# untitled.net
KiCad netlist of a schematic drawn in EAGLE
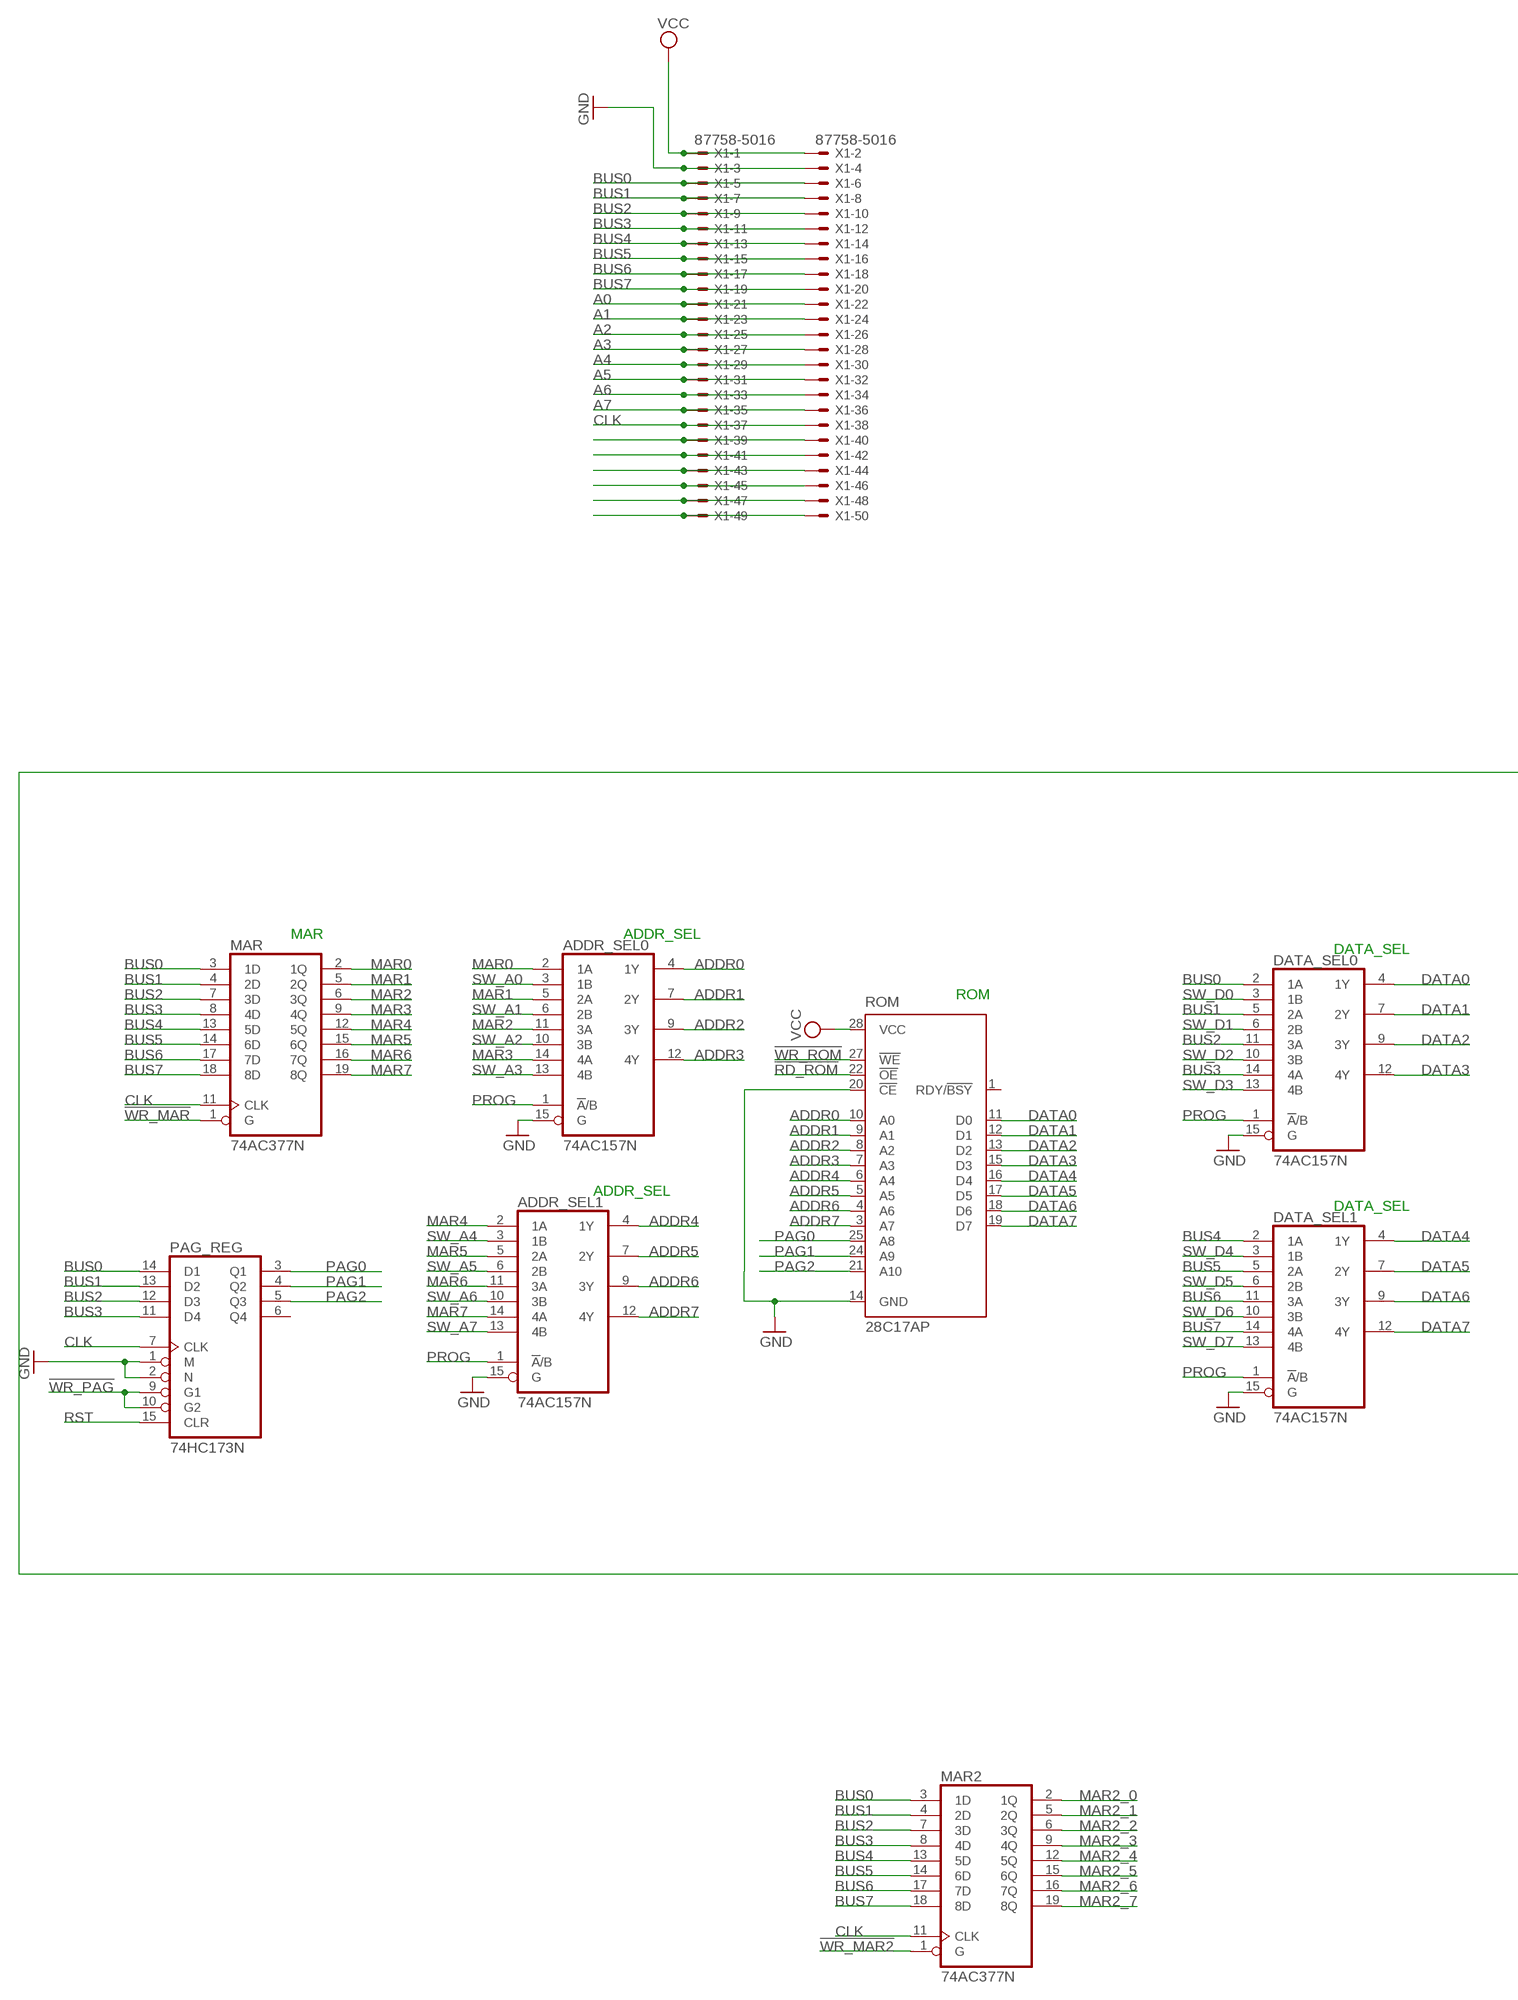
[diagram p0: schematic, sheet 1, part 1 of 2]
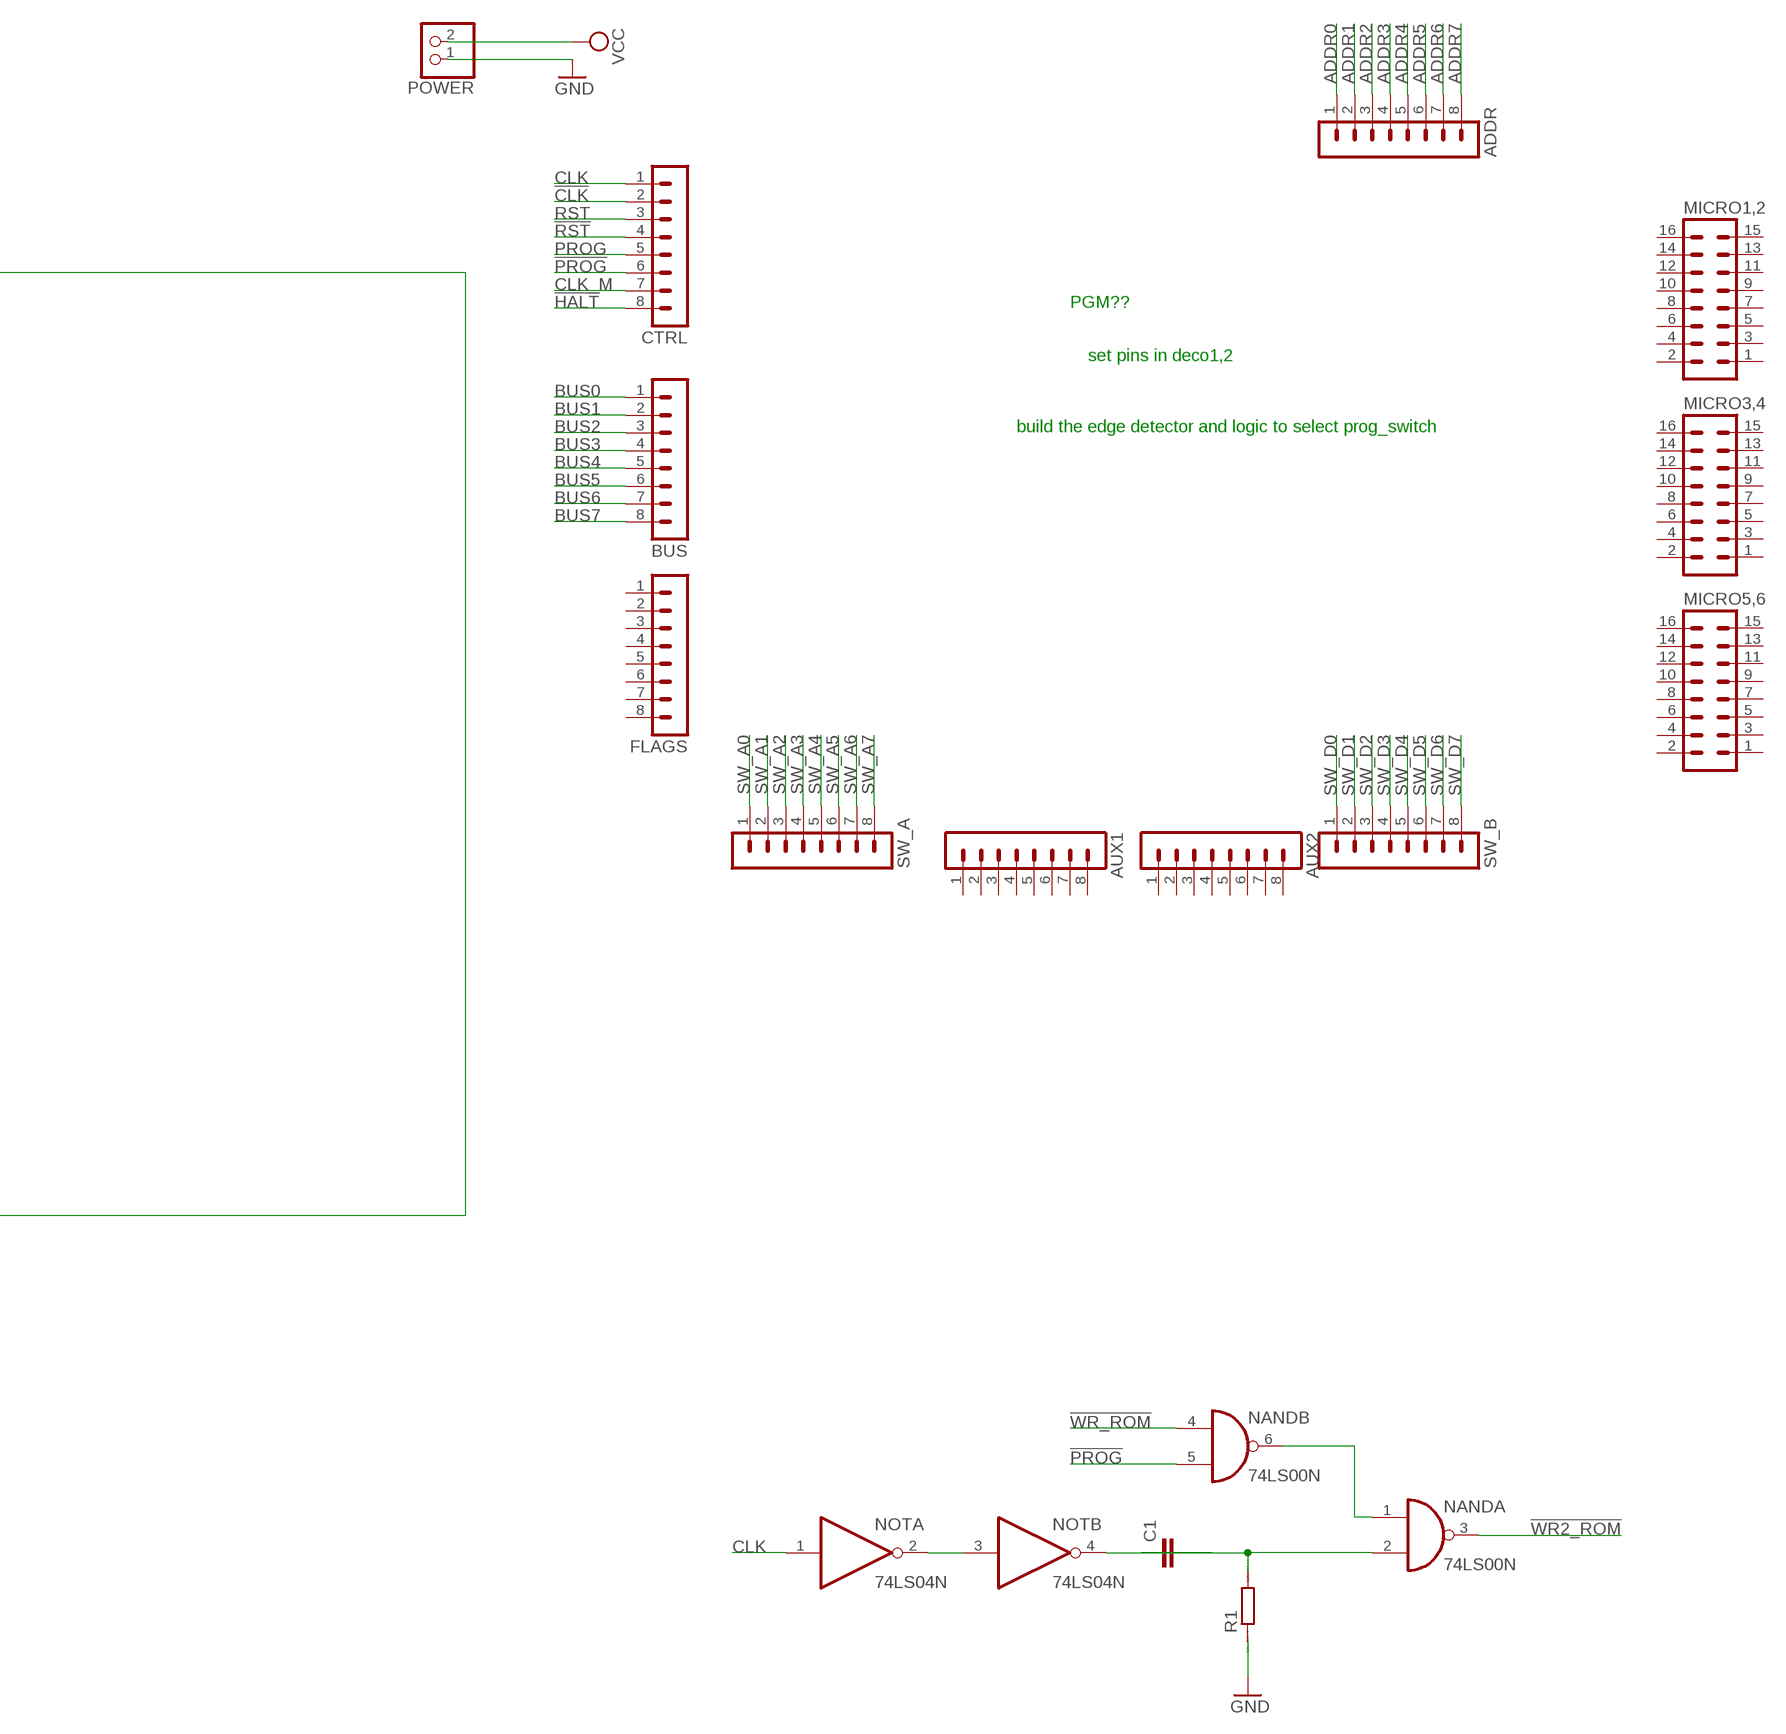
[diagram p1: schematic, sheet 1, part 2 of 2]

(export (version "E")
  (design (tool "Eeschema 10.0.6"))
  (components
    (comp (ref "ADDR")
      (value "MA08-1")
      (footprint "eagle-import:MA08-1")
      (libsource (lib "eagle-import") (part "MA08-1"))
    )
    (comp (ref "ADDR_SEL0")
      (value "74AC157N")
      (footprint "eagle-import:DIL16")
      (libsource (lib "eagle-import") (part "74157NAC"))
    )
    (comp (ref "ADDR_SEL1")
      (value "74AC157N")
      (footprint "eagle-import:DIL16")
      (libsource (lib "eagle-import") (part "74157NAC"))
    )
    (comp (ref "AUX1")
      (value "MA08-1")
      (footprint "eagle-import:MA08-1")
      (libsource (lib "eagle-import") (part "MA08-1"))
    )
    (comp (ref "AUX2")
      (value "MA08-1")
      (footprint "eagle-import:MA08-1")
      (libsource (lib "eagle-import") (part "MA08-1"))
    )
    (comp (ref "BUS")
      (value "MA08-1")
      (footprint "eagle-import:MA08-1")
      (libsource (lib "eagle-import") (part "MA08-1"))
    )
    (comp (ref "C1")
      (value "C2.5/4")
      (footprint "eagle-import:C2.5-4")
      (libsource (lib "eagle-import") (part "C2.5/4"))
    )
    (comp (ref "CTRL")
      (value "MA08-1")
      (footprint "eagle-import:MA08-1")
      (libsource (lib "eagle-import") (part "MA08-1"))
    )
    (comp (ref "DATA_SEL0")
      (value "74AC157N")
      (footprint "eagle-import:DIL16")
      (libsource (lib "eagle-import") (part "74157NAC"))
    )
    (comp (ref "DATA_SEL1")
      (value "74AC157N")
      (footprint "eagle-import:DIL16")
      (libsource (lib "eagle-import") (part "74157NAC"))
    )
    (comp (ref "FLAGS")
      (value "MA08-1")
      (footprint "eagle-import:MA08-1")
      (libsource (lib "eagle-import") (part "MA08-1"))
    )
    (comp (ref "MAR")
      (value "74AC377N")
      (footprint "eagle-import:DIL20")
      (libsource (lib "eagle-import") (part "74377NAC"))
    )
    (comp (ref "MAR2")
      (value "74AC377N")
      (footprint "eagle-import:DIL20")
      (libsource (lib "eagle-import") (part "74377NAC"))
    )
    (comp (ref "MICRO1,2")
      (value "MA08-2")
      (footprint "eagle-import:MA08-2")
      (libsource (lib "eagle-import") (part "MA08-2"))
    )
    (comp (ref "MICRO3,4")
      (value "MA08-2")
      (footprint "eagle-import:MA08-2")
      (libsource (lib "eagle-import") (part "MA08-2"))
    )
    (comp (ref "MICRO5,6")
      (value "MA08-2")
      (footprint "eagle-import:MA08-2")
      (libsource (lib "eagle-import") (part "MA08-2"))
    )
    (comp (ref "NAND")
      (value "74LS00N")
      (footprint "eagle-import:DIL14")
      (libsource (lib "eagle-import") (part "7400NLS"))
    )
    (comp (ref "NOT")
      (value "74LS04N")
      (footprint "eagle-import:DIL14")
      (libsource (lib "eagle-import") (part "7404NLS"))
    )
    (comp (ref "PAG_REG")
      (value "74HC173N")
      (footprint "eagle-import:DIL16")
      (libsource (lib "eagle-import") (part "74173NHC"))
    )
    (comp (ref "POWER")
      (value "PINHD-1X2")
      (footprint "eagle-import:1X02")
      (libsource (lib "eagle-import") (part "PINHD-1X2"))
    )
    (comp (ref "R1")
      (value "R0207/10")
      (footprint "eagle-import:0207_10")
      (libsource (lib "eagle-import") (part "R0207/10"))
    )
    (comp (ref "ROM")
      (value "28C17AP")
      (footprint "eagle-import:DIL28-6")
      (fields (field (name "MPN") "CAT28C17ALI20"))
      (libsource (lib "eagle-import") (part "2817APC"))
    )
    (comp (ref "SW_A")
      (value "MA08-1")
      (footprint "eagle-import:MA08-1")
      (libsource (lib "eagle-import") (part "MA08-1"))
    )
    (comp (ref "SW_B")
      (value "MA08-1")
      (footprint "eagle-import:MA08-1")
      (libsource (lib "eagle-import") (part "MA08-1"))
    )
    (comp (ref "X1")
      (value "87758-5016")
      (footprint "eagle-import:87758-5016")
      (fields (field (name "MF") "MOLEX"))
      (libsource (lib "eagle-import") (part "87758-5016"))
    )
  )
  (nets
    (net (code "1") (name "A0") (class "Default")
      (node (ref "X1") (pin "21") (pinfunction "S_21") (pintype "passive"))
      (node (ref "X1") (pin "22") (pinfunction "S_22") (pintype "passive"))
    )
    (net (code "2") (name "A1") (class "Default")
      (node (ref "X1") (pin "23") (pinfunction "S_23") (pintype "passive"))
      (node (ref "X1") (pin "24") (pinfunction "S_24") (pintype "passive"))
    )
    (net (code "3") (name "A2") (class "Default")
      (node (ref "X1") (pin "25") (pinfunction "S_25") (pintype "passive"))
      (node (ref "X1") (pin "26") (pinfunction "S_26") (pintype "passive"))
    )
    (net (code "4") (name "A3") (class "Default")
      (node (ref "X1") (pin "27") (pinfunction "S_27") (pintype "passive"))
      (node (ref "X1") (pin "28") (pinfunction "S_28") (pintype "passive"))
    )
    (net (code "5") (name "A4") (class "Default")
      (node (ref "X1") (pin "29") (pinfunction "S_29") (pintype "passive"))
      (node (ref "X1") (pin "30") (pinfunction "S_30") (pintype "passive"))
    )
    (net (code "6") (name "A5") (class "Default")
      (node (ref "X1") (pin "31") (pinfunction "S_31") (pintype "passive"))
      (node (ref "X1") (pin "32") (pinfunction "S_32") (pintype "passive"))
    )
    (net (code "7") (name "A6") (class "Default")
      (node (ref "X1") (pin "33") (pinfunction "S_33") (pintype "passive"))
      (node (ref "X1") (pin "34") (pinfunction "S_34") (pintype "passive"))
    )
    (net (code "8") (name "A7") (class "Default")
      (node (ref "X1") (pin "35") (pinfunction "S_35") (pintype "passive"))
      (node (ref "X1") (pin "36") (pinfunction "S_36") (pintype "passive"))
    )
    (net (code "9") (name "ADDR0") (class "Default")
      (node (ref "ADDR") (pin "1") (pinfunction "1_1") (pintype "passive"))
      (node (ref "ADDR_SEL0") (pin "4") (pinfunction "1Y_4") (pintype "output"))
      (node (ref "ROM") (pin "10") (pinfunction "A0_10") (pintype "input"))
    )
    (net (code "10") (name "ADDR1") (class "Default")
      (node (ref "ADDR") (pin "2") (pinfunction "2_2") (pintype "passive"))
      (node (ref "ADDR_SEL0") (pin "7") (pinfunction "2Y_7") (pintype "output"))
      (node (ref "ROM") (pin "9") (pinfunction "A1_9") (pintype "input"))
    )
    (net (code "11") (name "ADDR2") (class "Default")
      (node (ref "ADDR") (pin "3") (pinfunction "3_3") (pintype "passive"))
      (node (ref "ADDR_SEL0") (pin "9") (pinfunction "3Y_9") (pintype "output"))
      (node (ref "ROM") (pin "8") (pinfunction "A2_8") (pintype "input"))
    )
    (net (code "12") (name "ADDR3") (class "Default")
      (node (ref "ADDR") (pin "4") (pinfunction "4_4") (pintype "passive"))
      (node (ref "ADDR_SEL0") (pin "12") (pinfunction "4Y_12") (pintype "output"))
      (node (ref "ROM") (pin "7") (pinfunction "A3_7") (pintype "input"))
    )
    (net (code "13") (name "ADDR4") (class "Default")
      (node (ref "ADDR") (pin "5") (pinfunction "5_5") (pintype "passive"))
      (node (ref "ADDR_SEL1") (pin "4") (pinfunction "1Y_4") (pintype "output"))
      (node (ref "ROM") (pin "6") (pinfunction "A4_6") (pintype "input"))
    )
    (net (code "14") (name "ADDR5") (class "Default")
      (node (ref "ADDR") (pin "6") (pinfunction "6_6") (pintype "passive"))
      (node (ref "ADDR_SEL1") (pin "7") (pinfunction "2Y_7") (pintype "output"))
      (node (ref "ROM") (pin "5") (pinfunction "A5_5") (pintype "input"))
    )
    (net (code "15") (name "ADDR6") (class "Default")
      (node (ref "ADDR") (pin "7") (pinfunction "7_7") (pintype "passive"))
      (node (ref "ADDR_SEL1") (pin "9") (pinfunction "3Y_9") (pintype "output"))
      (node (ref "ROM") (pin "4") (pinfunction "A6_4") (pintype "input"))
    )
    (net (code "16") (name "ADDR7") (class "Default")
      (node (ref "ADDR") (pin "8") (pinfunction "8_8") (pintype "passive"))
      (node (ref "ADDR_SEL1") (pin "12") (pinfunction "4Y_12") (pintype "output"))
      (node (ref "ROM") (pin "3") (pinfunction "A7_3") (pintype "input"))
    )
    (net (code "17") (name "BUS0") (class "Default")
      (node (ref "BUS") (pin "1") (pinfunction "1_1") (pintype "passive"))
      (node (ref "DATA_SEL0") (pin "2") (pinfunction "1A_2") (pintype "input"))
      (node (ref "MAR") (pin "3") (pinfunction "1D_3") (pintype "input"))
      (node (ref "MAR2") (pin "3") (pinfunction "1D_3") (pintype "input"))
      (node (ref "PAG_REG") (pin "14") (pinfunction "D1_14") (pintype "input"))
      (node (ref "X1") (pin "5") (pinfunction "S_5") (pintype "passive"))
      (node (ref "X1") (pin "6") (pinfunction "S_6") (pintype "passive"))
    )
    (net (code "18") (name "BUS1") (class "Default")
      (node (ref "BUS") (pin "2") (pinfunction "2_2") (pintype "passive"))
      (node (ref "DATA_SEL0") (pin "5") (pinfunction "2A_5") (pintype "input"))
      (node (ref "MAR") (pin "4") (pinfunction "2D_4") (pintype "input"))
      (node (ref "MAR2") (pin "4") (pinfunction "2D_4") (pintype "input"))
      (node (ref "PAG_REG") (pin "13") (pinfunction "D2_13") (pintype "input"))
      (node (ref "X1") (pin "7") (pinfunction "S_7") (pintype "passive"))
      (node (ref "X1") (pin "8") (pinfunction "S_8") (pintype "passive"))
    )
    (net (code "19") (name "BUS2") (class "Default")
      (node (ref "BUS") (pin "3") (pinfunction "3_3") (pintype "passive"))
      (node (ref "DATA_SEL0") (pin "11") (pinfunction "3A_11") (pintype "input"))
      (node (ref "MAR") (pin "7") (pinfunction "3D_7") (pintype "input"))
      (node (ref "MAR2") (pin "7") (pinfunction "3D_7") (pintype "input"))
      (node (ref "PAG_REG") (pin "12") (pinfunction "D3_12") (pintype "input"))
      (node (ref "X1") (pin "10") (pinfunction "S_10") (pintype "passive"))
      (node (ref "X1") (pin "9") (pinfunction "S_9") (pintype "passive"))
    )
    (net (code "20") (name "BUS3") (class "Default")
      (node (ref "BUS") (pin "4") (pinfunction "4_4") (pintype "passive"))
      (node (ref "DATA_SEL0") (pin "14") (pinfunction "4A_14") (pintype "input"))
      (node (ref "MAR") (pin "8") (pinfunction "4D_8") (pintype "input"))
      (node (ref "MAR2") (pin "8") (pinfunction "4D_8") (pintype "input"))
      (node (ref "PAG_REG") (pin "11") (pinfunction "D4_11") (pintype "input"))
      (node (ref "X1") (pin "11") (pinfunction "S_11") (pintype "passive"))
      (node (ref "X1") (pin "12") (pinfunction "S_12") (pintype "passive"))
    )
    (net (code "21") (name "BUS4") (class "Default")
      (node (ref "BUS") (pin "5") (pinfunction "5_5") (pintype "passive"))
      (node (ref "DATA_SEL1") (pin "2") (pinfunction "1A_2") (pintype "input"))
      (node (ref "MAR") (pin "13") (pinfunction "5D_13") (pintype "input"))
      (node (ref "MAR2") (pin "13") (pinfunction "5D_13") (pintype "input"))
      (node (ref "X1") (pin "13") (pinfunction "S_13") (pintype "passive"))
      (node (ref "X1") (pin "14") (pinfunction "S_14") (pintype "passive"))
    )
    (net (code "22") (name "BUS5") (class "Default")
      (node (ref "BUS") (pin "6") (pinfunction "6_6") (pintype "passive"))
      (node (ref "DATA_SEL1") (pin "5") (pinfunction "2A_5") (pintype "input"))
      (node (ref "MAR") (pin "14") (pinfunction "6D_14") (pintype "input"))
      (node (ref "MAR2") (pin "14") (pinfunction "6D_14") (pintype "input"))
      (node (ref "X1") (pin "15") (pinfunction "S_15") (pintype "passive"))
      (node (ref "X1") (pin "16") (pinfunction "S_16") (pintype "passive"))
    )
    (net (code "23") (name "BUS6") (class "Default")
      (node (ref "BUS") (pin "7") (pinfunction "7_7") (pintype "passive"))
      (node (ref "DATA_SEL1") (pin "11") (pinfunction "3A_11") (pintype "input"))
      (node (ref "MAR") (pin "17") (pinfunction "7D_17") (pintype "input"))
      (node (ref "MAR2") (pin "17") (pinfunction "7D_17") (pintype "input"))
      (node (ref "X1") (pin "17") (pinfunction "S_17") (pintype "passive"))
      (node (ref "X1") (pin "18") (pinfunction "S_18") (pintype "passive"))
    )
    (net (code "24") (name "BUS7") (class "Default")
      (node (ref "BUS") (pin "8") (pinfunction "8_8") (pintype "passive"))
      (node (ref "DATA_SEL1") (pin "14") (pinfunction "4A_14") (pintype "input"))
      (node (ref "MAR") (pin "18") (pinfunction "8D_18") (pintype "input"))
      (node (ref "MAR2") (pin "18") (pinfunction "8D_18") (pintype "input"))
      (node (ref "X1") (pin "19") (pinfunction "S_19") (pintype "passive"))
      (node (ref "X1") (pin "20") (pinfunction "S_20") (pintype "passive"))
    )
    (net (code "25") (name "CLK") (class "Default")
      (node (ref "CTRL") (pin "1") (pinfunction "1_1") (pintype "passive"))
      (node (ref "MAR") (pin "11") (pinfunction "CLK_11") (pintype "input"))
      (node (ref "MAR2") (pin "11") (pinfunction "CLK_11") (pintype "input"))
      (node (ref "NOT") (pin "1") (pinfunction "I_1") (pintype "input"))
      (node (ref "PAG_REG") (pin "7") (pinfunction "CLK_7") (pintype "input"))
      (node (ref "X1") (pin "37") (pinfunction "S_37") (pintype "passive"))
      (node (ref "X1") (pin "38") (pinfunction "S_38") (pintype "passive"))
    )
    (net (code "26") (name "CLK_M") (class "Default")
      (node (ref "CTRL") (pin "7") (pinfunction "7_7") (pintype "passive"))
    )
    (net (code "27") (name "DATA0") (class "Default")
      (node (ref "DATA_SEL0") (pin "4") (pinfunction "1Y_4") (pintype "output"))
      (node (ref "ROM") (pin "11") (pinfunction "D0_11") (pintype "tri_state"))
    )
    (net (code "28") (name "DATA1") (class "Default")
      (node (ref "DATA_SEL0") (pin "7") (pinfunction "2Y_7") (pintype "output"))
      (node (ref "ROM") (pin "12") (pinfunction "D1_12") (pintype "tri_state"))
    )
    (net (code "29") (name "DATA2") (class "Default")
      (node (ref "DATA_SEL0") (pin "9") (pinfunction "3Y_9") (pintype "output"))
      (node (ref "ROM") (pin "13") (pinfunction "D2_13") (pintype "tri_state"))
    )
    (net (code "30") (name "DATA3") (class "Default")
      (node (ref "DATA_SEL0") (pin "12") (pinfunction "4Y_12") (pintype "output"))
      (node (ref "ROM") (pin "15") (pinfunction "D3_15") (pintype "tri_state"))
    )
    (net (code "31") (name "DATA4") (class "Default")
      (node (ref "DATA_SEL1") (pin "4") (pinfunction "1Y_4") (pintype "output"))
      (node (ref "ROM") (pin "16") (pinfunction "D4_16") (pintype "tri_state"))
    )
    (net (code "32") (name "DATA5") (class "Default")
      (node (ref "DATA_SEL1") (pin "7") (pinfunction "2Y_7") (pintype "output"))
      (node (ref "ROM") (pin "17") (pinfunction "D5_17") (pintype "tri_state"))
    )
    (net (code "33") (name "DATA6") (class "Default")
      (node (ref "DATA_SEL1") (pin "9") (pinfunction "3Y_9") (pintype "output"))
      (node (ref "ROM") (pin "18") (pinfunction "D6_18") (pintype "tri_state"))
    )
    (net (code "34") (name "DATA7") (class "Default")
      (node (ref "DATA_SEL1") (pin "12") (pinfunction "4Y_12") (pintype "output"))
      (node (ref "ROM") (pin "19") (pinfunction "D7_19") (pintype "tri_state"))
    )
    (net (code "35") (name "GND") (class "Default")
      (node (ref "ADDR_SEL0") (pin "15") (pinfunction "G_15") (pintype "input"))
      (node (ref "ADDR_SEL1") (pin "15") (pinfunction "G_15") (pintype "input"))
      (node (ref "DATA_SEL0") (pin "15") (pinfunction "G_15") (pintype "input"))
      (node (ref "DATA_SEL1") (pin "15") (pinfunction "G_15") (pintype "input"))
      (node (ref "PAG_REG") (pin "1") (pinfunction "M_1") (pintype "input"))
      (node (ref "PAG_REG") (pin "2") (pinfunction "N_2") (pintype "input"))
      (node (ref "POWER") (pin "1") (pinfunction "1_1") (pintype "passive"))
      (node (ref "R1") (pin "1") (pinfunction "1_1") (pintype "passive"))
      (node (ref "ROM") (pin "14") (pinfunction "GND_14") (pintype "power_in"))
      (node (ref "ROM") (pin "20") (pinfunction "~{CE}_20") (pintype "input"))
      (node (ref "X1") (pin "3") (pinfunction "S_3") (pintype "passive"))
      (node (ref "X1") (pin "4") (pinfunction "S_4") (pintype "passive"))
    )
    (net (code "36") (name "MAR0") (class "Default")
      (node (ref "ADDR_SEL0") (pin "2") (pinfunction "1A_2") (pintype "input"))
      (node (ref "MAR") (pin "2") (pinfunction "1Q_2") (pintype "output"))
    )
    (net (code "37") (name "MAR1") (class "Default")
      (node (ref "ADDR_SEL0") (pin "5") (pinfunction "2A_5") (pintype "input"))
      (node (ref "MAR") (pin "5") (pinfunction "2Q_5") (pintype "output"))
    )
    (net (code "38") (name "MAR2") (class "Default")
      (node (ref "ADDR_SEL0") (pin "11") (pinfunction "3A_11") (pintype "input"))
      (node (ref "MAR") (pin "6") (pinfunction "3Q_6") (pintype "output"))
    )
    (net (code "39") (name "MAR2_0") (class "Default")
      (node (ref "MAR2") (pin "2") (pinfunction "1Q_2") (pintype "output"))
    )
    (net (code "40") (name "MAR2_1") (class "Default")
      (node (ref "MAR2") (pin "5") (pinfunction "2Q_5") (pintype "output"))
    )
    (net (code "41") (name "MAR2_2") (class "Default")
      (node (ref "MAR2") (pin "6") (pinfunction "3Q_6") (pintype "output"))
    )
    (net (code "42") (name "MAR2_3") (class "Default")
      (node (ref "MAR2") (pin "9") (pinfunction "4Q_9") (pintype "output"))
    )
    (net (code "43") (name "MAR2_4") (class "Default")
      (node (ref "MAR2") (pin "12") (pinfunction "5Q_12") (pintype "output"))
    )
    (net (code "44") (name "MAR2_5") (class "Default")
      (node (ref "MAR2") (pin "15") (pinfunction "6Q_15") (pintype "output"))
    )
    (net (code "45") (name "MAR2_6") (class "Default")
      (node (ref "MAR2") (pin "16") (pinfunction "7Q_16") (pintype "output"))
    )
    (net (code "46") (name "MAR2_7") (class "Default")
      (node (ref "MAR2") (pin "19") (pinfunction "8Q_19") (pintype "output"))
    )
    (net (code "47") (name "MAR3") (class "Default")
      (node (ref "ADDR_SEL0") (pin "14") (pinfunction "4A_14") (pintype "input"))
      (node (ref "MAR") (pin "9") (pinfunction "4Q_9") (pintype "output"))
    )
    (net (code "48") (name "MAR4") (class "Default")
      (node (ref "ADDR_SEL1") (pin "2") (pinfunction "1A_2") (pintype "input"))
      (node (ref "MAR") (pin "12") (pinfunction "5Q_12") (pintype "output"))
    )
    (net (code "49") (name "MAR5") (class "Default")
      (node (ref "ADDR_SEL1") (pin "5") (pinfunction "2A_5") (pintype "input"))
      (node (ref "MAR") (pin "15") (pinfunction "6Q_15") (pintype "output"))
    )
    (net (code "50") (name "MAR6") (class "Default")
      (node (ref "ADDR_SEL1") (pin "11") (pinfunction "3A_11") (pintype "input"))
      (node (ref "MAR") (pin "16") (pinfunction "7Q_16") (pintype "output"))
    )
    (net (code "51") (name "MAR7") (class "Default")
      (node (ref "ADDR_SEL1") (pin "14") (pinfunction "4A_14") (pintype "input"))
      (node (ref "MAR") (pin "19") (pinfunction "8Q_19") (pintype "output"))
    )
    (net (code "52") (name "Net-(NANDA-I0)") (class "Default")
      (node (ref "NAND") (pin "1") (pinfunction "I0_1") (pintype "input"))
      (node (ref "NAND") (pin "6") (pinfunction "O_6") (pintype "output"))
    )
    (net (code "53") (name "Net-(NANDA-I1)") (class "Default")
      (node (ref "C1") (pin "2") (pinfunction "2_2") (pintype "passive"))
      (node (ref "NAND") (pin "2") (pinfunction "I1_2") (pintype "input"))
      (node (ref "R1") (pin "2") (pinfunction "2_2") (pintype "passive"))
    )
    (net (code "54") (name "Net-(NOTA-O)") (class "Default")
      (node (ref "NOT") (pin "2") (pinfunction "O_2") (pintype "output"))
      (node (ref "NOT") (pin "3") (pinfunction "I_3") (pintype "input"))
    )
    (net (code "55") (name "Net-(NOTB-O)") (class "Default")
      (node (ref "C1") (pin "1") (pinfunction "1_1") (pintype "passive"))
      (node (ref "NOT") (pin "4") (pinfunction "O_4") (pintype "output"))
    )
    (net (code "56") (name "Net-(X1AG-S)") (class "Default")
      (node (ref "X1") (pin "39") (pinfunction "S_39") (pintype "passive"))
      (node (ref "X1") (pin "40") (pinfunction "S_40") (pintype "passive"))
    )
    (net (code "57") (name "Net-(X1AJ-S)") (class "Default")
      (node (ref "X1") (pin "41") (pinfunction "S_41") (pintype "passive"))
      (node (ref "X1") (pin "42") (pinfunction "S_42") (pintype "passive"))
    )
    (net (code "58") (name "Net-(X1AL-S)") (class "Default")
      (node (ref "X1") (pin "43") (pinfunction "S_43") (pintype "passive"))
      (node (ref "X1") (pin "44") (pinfunction "S_44") (pintype "passive"))
    )
    (net (code "59") (name "Net-(X1AN-S)") (class "Default")
      (node (ref "X1") (pin "45") (pinfunction "S_45") (pintype "passive"))
      (node (ref "X1") (pin "46") (pinfunction "S_46") (pintype "passive"))
    )
    (net (code "60") (name "Net-(X1AP-S)") (class "Default")
      (node (ref "X1") (pin "47") (pinfunction "S_47") (pintype "passive"))
      (node (ref "X1") (pin "48") (pinfunction "S_48") (pintype "passive"))
    )
    (net (code "61") (name "Net-(X1AR-S)") (class "Default")
      (node (ref "X1") (pin "49") (pinfunction "S_49") (pintype "passive"))
      (node (ref "X1") (pin "50") (pinfunction "S_50") (pintype "passive"))
    )
    (net (code "62") (name "PAG0") (class "Default")
      (node (ref "PAG_REG") (pin "3") (pinfunction "Q1_3") (pintype "tri_state"))
      (node (ref "ROM") (pin "25") (pinfunction "A8_25") (pintype "input"))
    )
    (net (code "63") (name "PAG1") (class "Default")
      (node (ref "PAG_REG") (pin "4") (pinfunction "Q2_4") (pintype "tri_state"))
      (node (ref "ROM") (pin "24") (pinfunction "A9_24") (pintype "input"))
    )
    (net (code "64") (name "PAG2") (class "Default")
      (node (ref "PAG_REG") (pin "5") (pinfunction "Q3_5") (pintype "tri_state"))
      (node (ref "ROM") (pin "21") (pinfunction "A10_21") (pintype "input"))
    )
    (net (code "65") (name "PROG") (class "Default")
      (node (ref "ADDR_SEL0") (pin "1") (pinfunction "~{A}/B_1") (pintype "input"))
      (node (ref "ADDR_SEL1") (pin "1") (pinfunction "~{A}/B_1") (pintype "input"))
      (node (ref "CTRL") (pin "5") (pinfunction "5_5") (pintype "passive"))
      (node (ref "DATA_SEL0") (pin "1") (pinfunction "~{A}/B_1") (pintype "input"))
      (node (ref "DATA_SEL1") (pin "1") (pinfunction "~{A}/B_1") (pintype "input"))
    )
    (net (code "66") (name "RST") (class "Default")
      (node (ref "CTRL") (pin "3") (pinfunction "3_3") (pintype "passive"))
      (node (ref "PAG_REG") (pin "15") (pinfunction "CLR_15") (pintype "input"))
    )
    (net (code "67") (name "SW_A0") (class "Default")
      (node (ref "ADDR_SEL0") (pin "3") (pinfunction "1B_3") (pintype "input"))
      (node (ref "SW_A") (pin "1") (pinfunction "1_1") (pintype "passive"))
    )
    (net (code "68") (name "SW_A1") (class "Default")
      (node (ref "ADDR_SEL0") (pin "6") (pinfunction "2B_6") (pintype "input"))
      (node (ref "SW_A") (pin "2") (pinfunction "2_2") (pintype "passive"))
    )
    (net (code "69") (name "SW_A2") (class "Default")
      (node (ref "ADDR_SEL0") (pin "10") (pinfunction "3B_10") (pintype "input"))
      (node (ref "SW_A") (pin "3") (pinfunction "3_3") (pintype "passive"))
    )
    (net (code "70") (name "SW_A3") (class "Default")
      (node (ref "ADDR_SEL0") (pin "13") (pinfunction "4B_13") (pintype "input"))
      (node (ref "SW_A") (pin "4") (pinfunction "4_4") (pintype "passive"))
    )
    (net (code "71") (name "SW_A4") (class "Default")
      (node (ref "ADDR_SEL1") (pin "3") (pinfunction "1B_3") (pintype "input"))
      (node (ref "SW_A") (pin "5") (pinfunction "5_5") (pintype "passive"))
    )
    (net (code "72") (name "SW_A5") (class "Default")
      (node (ref "ADDR_SEL1") (pin "6") (pinfunction "2B_6") (pintype "input"))
      (node (ref "SW_A") (pin "6") (pinfunction "6_6") (pintype "passive"))
    )
    (net (code "73") (name "SW_A6") (class "Default")
      (node (ref "ADDR_SEL1") (pin "10") (pinfunction "3B_10") (pintype "input"))
      (node (ref "SW_A") (pin "7") (pinfunction "7_7") (pintype "passive"))
    )
    (net (code "74") (name "SW_A7") (class "Default")
      (node (ref "ADDR_SEL1") (pin "13") (pinfunction "4B_13") (pintype "input"))
      (node (ref "SW_A") (pin "8") (pinfunction "8_8") (pintype "passive"))
    )
    (net (code "75") (name "SW_D0") (class "Default")
      (node (ref "DATA_SEL0") (pin "3") (pinfunction "1B_3") (pintype "input"))
      (node (ref "SW_B") (pin "1") (pinfunction "1_1") (pintype "passive"))
    )
    (net (code "76") (name "SW_D1") (class "Default")
      (node (ref "DATA_SEL0") (pin "6") (pinfunction "2B_6") (pintype "input"))
      (node (ref "SW_B") (pin "2") (pinfunction "2_2") (pintype "passive"))
    )
    (net (code "77") (name "SW_D2") (class "Default")
      (node (ref "DATA_SEL0") (pin "10") (pinfunction "3B_10") (pintype "input"))
      (node (ref "SW_B") (pin "3") (pinfunction "3_3") (pintype "passive"))
    )
    (net (code "78") (name "SW_D3") (class "Default")
      (node (ref "DATA_SEL0") (pin "13") (pinfunction "4B_13") (pintype "input"))
      (node (ref "SW_B") (pin "4") (pinfunction "4_4") (pintype "passive"))
    )
    (net (code "79") (name "SW_D4") (class "Default")
      (node (ref "DATA_SEL1") (pin "3") (pinfunction "1B_3") (pintype "input"))
      (node (ref "SW_B") (pin "5") (pinfunction "5_5") (pintype "passive"))
    )
    (net (code "80") (name "SW_D5") (class "Default")
      (node (ref "DATA_SEL1") (pin "6") (pinfunction "2B_6") (pintype "input"))
      (node (ref "SW_B") (pin "6") (pinfunction "6_6") (pintype "passive"))
    )
    (net (code "81") (name "SW_D6") (class "Default")
      (node (ref "DATA_SEL1") (pin "10") (pinfunction "3B_10") (pintype "input"))
      (node (ref "SW_B") (pin "7") (pinfunction "7_7") (pintype "passive"))
    )
    (net (code "82") (name "SW_D7") (class "Default")
      (node (ref "DATA_SEL1") (pin "13") (pinfunction "4B_13") (pintype "input"))
      (node (ref "SW_B") (pin "8") (pinfunction "8_8") (pintype "passive"))
    )
    (net (code "83") (name "VCC") (class "Default")
      (node (ref "POWER") (pin "2") (pinfunction "2_2") (pintype "passive"))
      (node (ref "ROM") (pin "28") (pinfunction "VCC_28") (pintype "power_in"))
      (node (ref "X1") (pin "1") (pinfunction "S_1") (pintype "passive"))
      (node (ref "X1") (pin "2") (pinfunction "S_2") (pintype "passive"))
    )
    (net (code "84") (name "unconnected-(AUX1-Pad1)") (class "Default")
      (node (ref "AUX1") (pin "1") (pinfunction "1_1") (pintype "passive"))
    )
    (net (code "85") (name "unconnected-(AUX1-Pad2)") (class "Default")
      (node (ref "AUX1") (pin "2") (pinfunction "2_2") (pintype "passive"))
    )
    (net (code "86") (name "unconnected-(AUX1-Pad3)") (class "Default")
      (node (ref "AUX1") (pin "3") (pinfunction "3_3") (pintype "passive"))
    )
    (net (code "87") (name "unconnected-(AUX1-Pad4)") (class "Default")
      (node (ref "AUX1") (pin "4") (pinfunction "4_4") (pintype "passive"))
    )
    (net (code "88") (name "unconnected-(AUX1-Pad5)") (class "Default")
      (node (ref "AUX1") (pin "5") (pinfunction "5_5") (pintype "passive"))
    )
    (net (code "89") (name "unconnected-(AUX1-Pad6)") (class "Default")
      (node (ref "AUX1") (pin "6") (pinfunction "6_6") (pintype "passive"))
    )
    (net (code "90") (name "unconnected-(AUX1-Pad7)") (class "Default")
      (node (ref "AUX1") (pin "7") (pinfunction "7_7") (pintype "passive"))
    )
    (net (code "91") (name "unconnected-(AUX1-Pad8)") (class "Default")
      (node (ref "AUX1") (pin "8") (pinfunction "8_8") (pintype "passive"))
    )
    (net (code "92") (name "unconnected-(AUX2-Pad1)") (class "Default")
      (node (ref "AUX2") (pin "1") (pinfunction "1_1") (pintype "passive"))
    )
    (net (code "93") (name "unconnected-(AUX2-Pad2)") (class "Default")
      (node (ref "AUX2") (pin "2") (pinfunction "2_2") (pintype "passive"))
    )
    (net (code "94") (name "unconnected-(AUX2-Pad3)") (class "Default")
      (node (ref "AUX2") (pin "3") (pinfunction "3_3") (pintype "passive"))
    )
    (net (code "95") (name "unconnected-(AUX2-Pad4)") (class "Default")
      (node (ref "AUX2") (pin "4") (pinfunction "4_4") (pintype "passive"))
    )
    (net (code "96") (name "unconnected-(AUX2-Pad5)") (class "Default")
      (node (ref "AUX2") (pin "5") (pinfunction "5_5") (pintype "passive"))
    )
    (net (code "97") (name "unconnected-(AUX2-Pad6)") (class "Default")
      (node (ref "AUX2") (pin "6") (pinfunction "6_6") (pintype "passive"))
    )
    (net (code "98") (name "unconnected-(AUX2-Pad7)") (class "Default")
      (node (ref "AUX2") (pin "7") (pinfunction "7_7") (pintype "passive"))
    )
    (net (code "99") (name "unconnected-(AUX2-Pad8)") (class "Default")
      (node (ref "AUX2") (pin "8") (pinfunction "8_8") (pintype "passive"))
    )
    (net (code "100") (name "unconnected-(FLAGS-Pad1)") (class "Default")
      (node (ref "FLAGS") (pin "1") (pinfunction "1_1") (pintype "passive"))
    )
    (net (code "101") (name "unconnected-(FLAGS-Pad2)") (class "Default")
      (node (ref "FLAGS") (pin "2") (pinfunction "2_2") (pintype "passive"))
    )
    (net (code "102") (name "unconnected-(FLAGS-Pad3)") (class "Default")
      (node (ref "FLAGS") (pin "3") (pinfunction "3_3") (pintype "passive"))
    )
    (net (code "103") (name "unconnected-(FLAGS-Pad4)") (class "Default")
      (node (ref "FLAGS") (pin "4") (pinfunction "4_4") (pintype "passive"))
    )
    (net (code "104") (name "unconnected-(FLAGS-Pad5)") (class "Default")
      (node (ref "FLAGS") (pin "5") (pinfunction "5_5") (pintype "passive"))
    )
    (net (code "105") (name "unconnected-(FLAGS-Pad6)") (class "Default")
      (node (ref "FLAGS") (pin "6") (pinfunction "6_6") (pintype "passive"))
    )
    (net (code "106") (name "unconnected-(FLAGS-Pad7)") (class "Default")
      (node (ref "FLAGS") (pin "7") (pinfunction "7_7") (pintype "passive"))
    )
    (net (code "107") (name "unconnected-(FLAGS-Pad8)") (class "Default")
      (node (ref "FLAGS") (pin "8") (pinfunction "8_8") (pintype "passive"))
    )
    (net (code "108") (name "unconnected-(MICRO1,2-Pad1)") (class "Default")
      (node (ref "MICRO1,2") (pin "1") (pinfunction "1_1") (pintype "passive"))
    )
    (net (code "109") (name "unconnected-(MICRO1,2-Pad2)") (class "Default")
      (node (ref "MICRO1,2") (pin "2") (pinfunction "2_2") (pintype "passive"))
    )
    (net (code "110") (name "unconnected-(MICRO1,2-Pad3)") (class "Default")
      (node (ref "MICRO1,2") (pin "3") (pinfunction "3_3") (pintype "passive"))
    )
    (net (code "111") (name "unconnected-(MICRO1,2-Pad4)") (class "Default")
      (node (ref "MICRO1,2") (pin "4") (pinfunction "4_4") (pintype "passive"))
    )
    (net (code "112") (name "unconnected-(MICRO1,2-Pad5)") (class "Default")
      (node (ref "MICRO1,2") (pin "5") (pinfunction "5_5") (pintype "passive"))
    )
    (net (code "113") (name "unconnected-(MICRO1,2-Pad6)") (class "Default")
      (node (ref "MICRO1,2") (pin "6") (pinfunction "6_6") (pintype "passive"))
    )
    (net (code "114") (name "unconnected-(MICRO1,2-Pad7)") (class "Default")
      (node (ref "MICRO1,2") (pin "7") (pinfunction "7_7") (pintype "passive"))
    )
    (net (code "115") (name "unconnected-(MICRO1,2-Pad8)") (class "Default")
      (node (ref "MICRO1,2") (pin "8") (pinfunction "8_8") (pintype "passive"))
    )
    (net (code "116") (name "unconnected-(MICRO1,2-Pad9)") (class "Default")
      (node (ref "MICRO1,2") (pin "9") (pinfunction "9_9") (pintype "passive"))
    )
    (net (code "117") (name "unconnected-(MICRO1,2-Pad10)") (class "Default")
      (node (ref "MICRO1,2") (pin "10") (pinfunction "10_10") (pintype "passive"))
    )
    (net (code "118") (name "unconnected-(MICRO1,2-Pad11)") (class "Default")
      (node (ref "MICRO1,2") (pin "11") (pinfunction "11_11") (pintype "passive"))
    )
    (net (code "119") (name "unconnected-(MICRO1,2-Pad12)") (class "Default")
      (node (ref "MICRO1,2") (pin "12") (pinfunction "12_12") (pintype "passive"))
    )
    (net (code "120") (name "unconnected-(MICRO1,2-Pad13)") (class "Default")
      (node (ref "MICRO1,2") (pin "13") (pinfunction "13_13") (pintype "passive"))
    )
    (net (code "121") (name "unconnected-(MICRO1,2-Pad14)") (class "Default")
      (node (ref "MICRO1,2") (pin "14") (pinfunction "14_14") (pintype "passive"))
    )
    (net (code "122") (name "unconnected-(MICRO1,2-Pad15)") (class "Default")
      (node (ref "MICRO1,2") (pin "15") (pinfunction "15_15") (pintype "passive"))
    )
    (net (code "123") (name "unconnected-(MICRO1,2-Pad16)") (class "Default")
      (node (ref "MICRO1,2") (pin "16") (pinfunction "16_16") (pintype "passive"))
    )
    (net (code "124") (name "unconnected-(MICRO3,4-Pad1)") (class "Default")
      (node (ref "MICRO3,4") (pin "1") (pinfunction "1_1") (pintype "passive"))
    )
    (net (code "125") (name "unconnected-(MICRO3,4-Pad2)") (class "Default")
      (node (ref "MICRO3,4") (pin "2") (pinfunction "2_2") (pintype "passive"))
    )
    (net (code "126") (name "unconnected-(MICRO3,4-Pad3)") (class "Default")
      (node (ref "MICRO3,4") (pin "3") (pinfunction "3_3") (pintype "passive"))
    )
    (net (code "127") (name "unconnected-(MICRO3,4-Pad4)") (class "Default")
      (node (ref "MICRO3,4") (pin "4") (pinfunction "4_4") (pintype "passive"))
    )
    (net (code "128") (name "unconnected-(MICRO3,4-Pad5)") (class "Default")
      (node (ref "MICRO3,4") (pin "5") (pinfunction "5_5") (pintype "passive"))
    )
    (net (code "129") (name "unconnected-(MICRO3,4-Pad6)") (class "Default")
      (node (ref "MICRO3,4") (pin "6") (pinfunction "6_6") (pintype "passive"))
    )
    (net (code "130") (name "unconnected-(MICRO3,4-Pad7)") (class "Default")
      (node (ref "MICRO3,4") (pin "7") (pinfunction "7_7") (pintype "passive"))
    )
    (net (code "131") (name "unconnected-(MICRO3,4-Pad8)") (class "Default")
      (node (ref "MICRO3,4") (pin "8") (pinfunction "8_8") (pintype "passive"))
    )
    (net (code "132") (name "unconnected-(MICRO3,4-Pad9)") (class "Default")
      (node (ref "MICRO3,4") (pin "9") (pinfunction "9_9") (pintype "passive"))
    )
    (net (code "133") (name "unconnected-(MICRO3,4-Pad10)") (class "Default")
      (node (ref "MICRO3,4") (pin "10") (pinfunction "10_10") (pintype "passive"))
    )
    (net (code "134") (name "unconnected-(MICRO3,4-Pad11)") (class "Default")
      (node (ref "MICRO3,4") (pin "11") (pinfunction "11_11") (pintype "passive"))
    )
    (net (code "135") (name "unconnected-(MICRO3,4-Pad12)") (class "Default")
      (node (ref "MICRO3,4") (pin "12") (pinfunction "12_12") (pintype "passive"))
    )
    (net (code "136") (name "unconnected-(MICRO3,4-Pad13)") (class "Default")
      (node (ref "MICRO3,4") (pin "13") (pinfunction "13_13") (pintype "passive"))
    )
    (net (code "137") (name "unconnected-(MICRO3,4-Pad14)") (class "Default")
      (node (ref "MICRO3,4") (pin "14") (pinfunction "14_14") (pintype "passive"))
    )
    (net (code "138") (name "unconnected-(MICRO3,4-Pad15)") (class "Default")
      (node (ref "MICRO3,4") (pin "15") (pinfunction "15_15") (pintype "passive"))
    )
    (net (code "139") (name "unconnected-(MICRO3,4-Pad16)") (class "Default")
      (node (ref "MICRO3,4") (pin "16") (pinfunction "16_16") (pintype "passive"))
    )
    (net (code "140") (name "unconnected-(MICRO5,6-Pad1)") (class "Default")
      (node (ref "MICRO5,6") (pin "1") (pinfunction "1_1") (pintype "passive"))
    )
    (net (code "141") (name "unconnected-(MICRO5,6-Pad2)") (class "Default")
      (node (ref "MICRO5,6") (pin "2") (pinfunction "2_2") (pintype "passive"))
    )
    (net (code "142") (name "unconnected-(MICRO5,6-Pad3)") (class "Default")
      (node (ref "MICRO5,6") (pin "3") (pinfunction "3_3") (pintype "passive"))
    )
    (net (code "143") (name "unconnected-(MICRO5,6-Pad4)") (class "Default")
      (node (ref "MICRO5,6") (pin "4") (pinfunction "4_4") (pintype "passive"))
    )
    (net (code "144") (name "unconnected-(MICRO5,6-Pad5)") (class "Default")
      (node (ref "MICRO5,6") (pin "5") (pinfunction "5_5") (pintype "passive"))
    )
    (net (code "145") (name "unconnected-(MICRO5,6-Pad6)") (class "Default")
      (node (ref "MICRO5,6") (pin "6") (pinfunction "6_6") (pintype "passive"))
    )
    (net (code "146") (name "unconnected-(MICRO5,6-Pad7)") (class "Default")
      (node (ref "MICRO5,6") (pin "7") (pinfunction "7_7") (pintype "passive"))
    )
    (net (code "147") (name "unconnected-(MICRO5,6-Pad8)") (class "Default")
      (node (ref "MICRO5,6") (pin "8") (pinfunction "8_8") (pintype "passive"))
    )
    (net (code "148") (name "unconnected-(MICRO5,6-Pad9)") (class "Default")
      (node (ref "MICRO5,6") (pin "9") (pinfunction "9_9") (pintype "passive"))
    )
    (net (code "149") (name "unconnected-(MICRO5,6-Pad10)") (class "Default")
      (node (ref "MICRO5,6") (pin "10") (pinfunction "10_10") (pintype "passive"))
    )
    (net (code "150") (name "unconnected-(MICRO5,6-Pad11)") (class "Default")
      (node (ref "MICRO5,6") (pin "11") (pinfunction "11_11") (pintype "passive"))
    )
    (net (code "151") (name "unconnected-(MICRO5,6-Pad12)") (class "Default")
      (node (ref "MICRO5,6") (pin "12") (pinfunction "12_12") (pintype "passive"))
    )
    (net (code "152") (name "unconnected-(MICRO5,6-Pad13)") (class "Default")
      (node (ref "MICRO5,6") (pin "13") (pinfunction "13_13") (pintype "passive"))
    )
    (net (code "153") (name "unconnected-(MICRO5,6-Pad14)") (class "Default")
      (node (ref "MICRO5,6") (pin "14") (pinfunction "14_14") (pintype "passive"))
    )
    (net (code "154") (name "unconnected-(MICRO5,6-Pad15)") (class "Default")
      (node (ref "MICRO5,6") (pin "15") (pinfunction "15_15") (pintype "passive"))
    )
    (net (code "155") (name "unconnected-(MICRO5,6-Pad16)") (class "Default")
      (node (ref "MICRO5,6") (pin "16") (pinfunction "16_16") (pintype "passive"))
    )
    (net (code "156") (name "unconnected-(PAG_REGA-Q4-Pad6)") (class "Default")
      (node (ref "PAG_REG") (pin "6") (pinfunction "Q4_6") (pintype "tri_state"))
    )
    (net (code "157") (name "unconnected-(ROMD-RDY{slash}~{BSY}-Pad1)") (class "Default")
      (node (ref "ROM") (pin "1") (pinfunction "RDY/~{BSY}_1") (pintype "output"))
    )
    (net (code "158") (name "~{CLK}") (class "Default")
      (node (ref "CTRL") (pin "2") (pinfunction "2_2") (pintype "passive"))
    )
    (net (code "159") (name "~{HALT}") (class "Default")
      (node (ref "CTRL") (pin "8") (pinfunction "8_8") (pintype "passive"))
    )
    (net (code "160") (name "~{PROG}") (class "Default")
      (node (ref "CTRL") (pin "6") (pinfunction "6_6") (pintype "passive"))
      (node (ref "NAND") (pin "5") (pinfunction "I1_5") (pintype "input"))
    )
    (net (code "161") (name "~{RD_ROM}") (class "Default")
      (node (ref "ROM") (pin "22") (pinfunction "~{OE}_22") (pintype "input"))
    )
    (net (code "162") (name "~{RST}") (class "Default")
      (node (ref "CTRL") (pin "4") (pinfunction "4_4") (pintype "passive"))
    )
    (net (code "163") (name "~{WR2_ROM}") (class "Default")
      (node (ref "NAND") (pin "3") (pinfunction "O_3") (pintype "output"))
    )
    (net (code "164") (name "~{WR_MAR2}") (class "Default")
      (node (ref "MAR2") (pin "1") (pinfunction "G_1") (pintype "input"))
    )
    (net (code "165") (name "~{WR_MAR}") (class "Default")
      (node (ref "MAR") (pin "1") (pinfunction "G_1") (pintype "input"))
    )
    (net (code "166") (name "~{WR_PAG}") (class "Default")
      (node (ref "PAG_REG") (pin "10") (pinfunction "G2_10") (pintype "input"))
      (node (ref "PAG_REG") (pin "9") (pinfunction "G1_9") (pintype "input"))
    )
    (net (code "167") (name "~{WR_ROM}") (class "Default")
      (node (ref "NAND") (pin "4") (pinfunction "I0_4") (pintype "input"))
      (node (ref "ROM") (pin "27") (pinfunction "~{WE}_27") (pintype "input"))
    )
  )
)
